# 25_LMS3_RX1_BB_ADC.net
KiCad netlist of a schematic drawn in Altium Designer
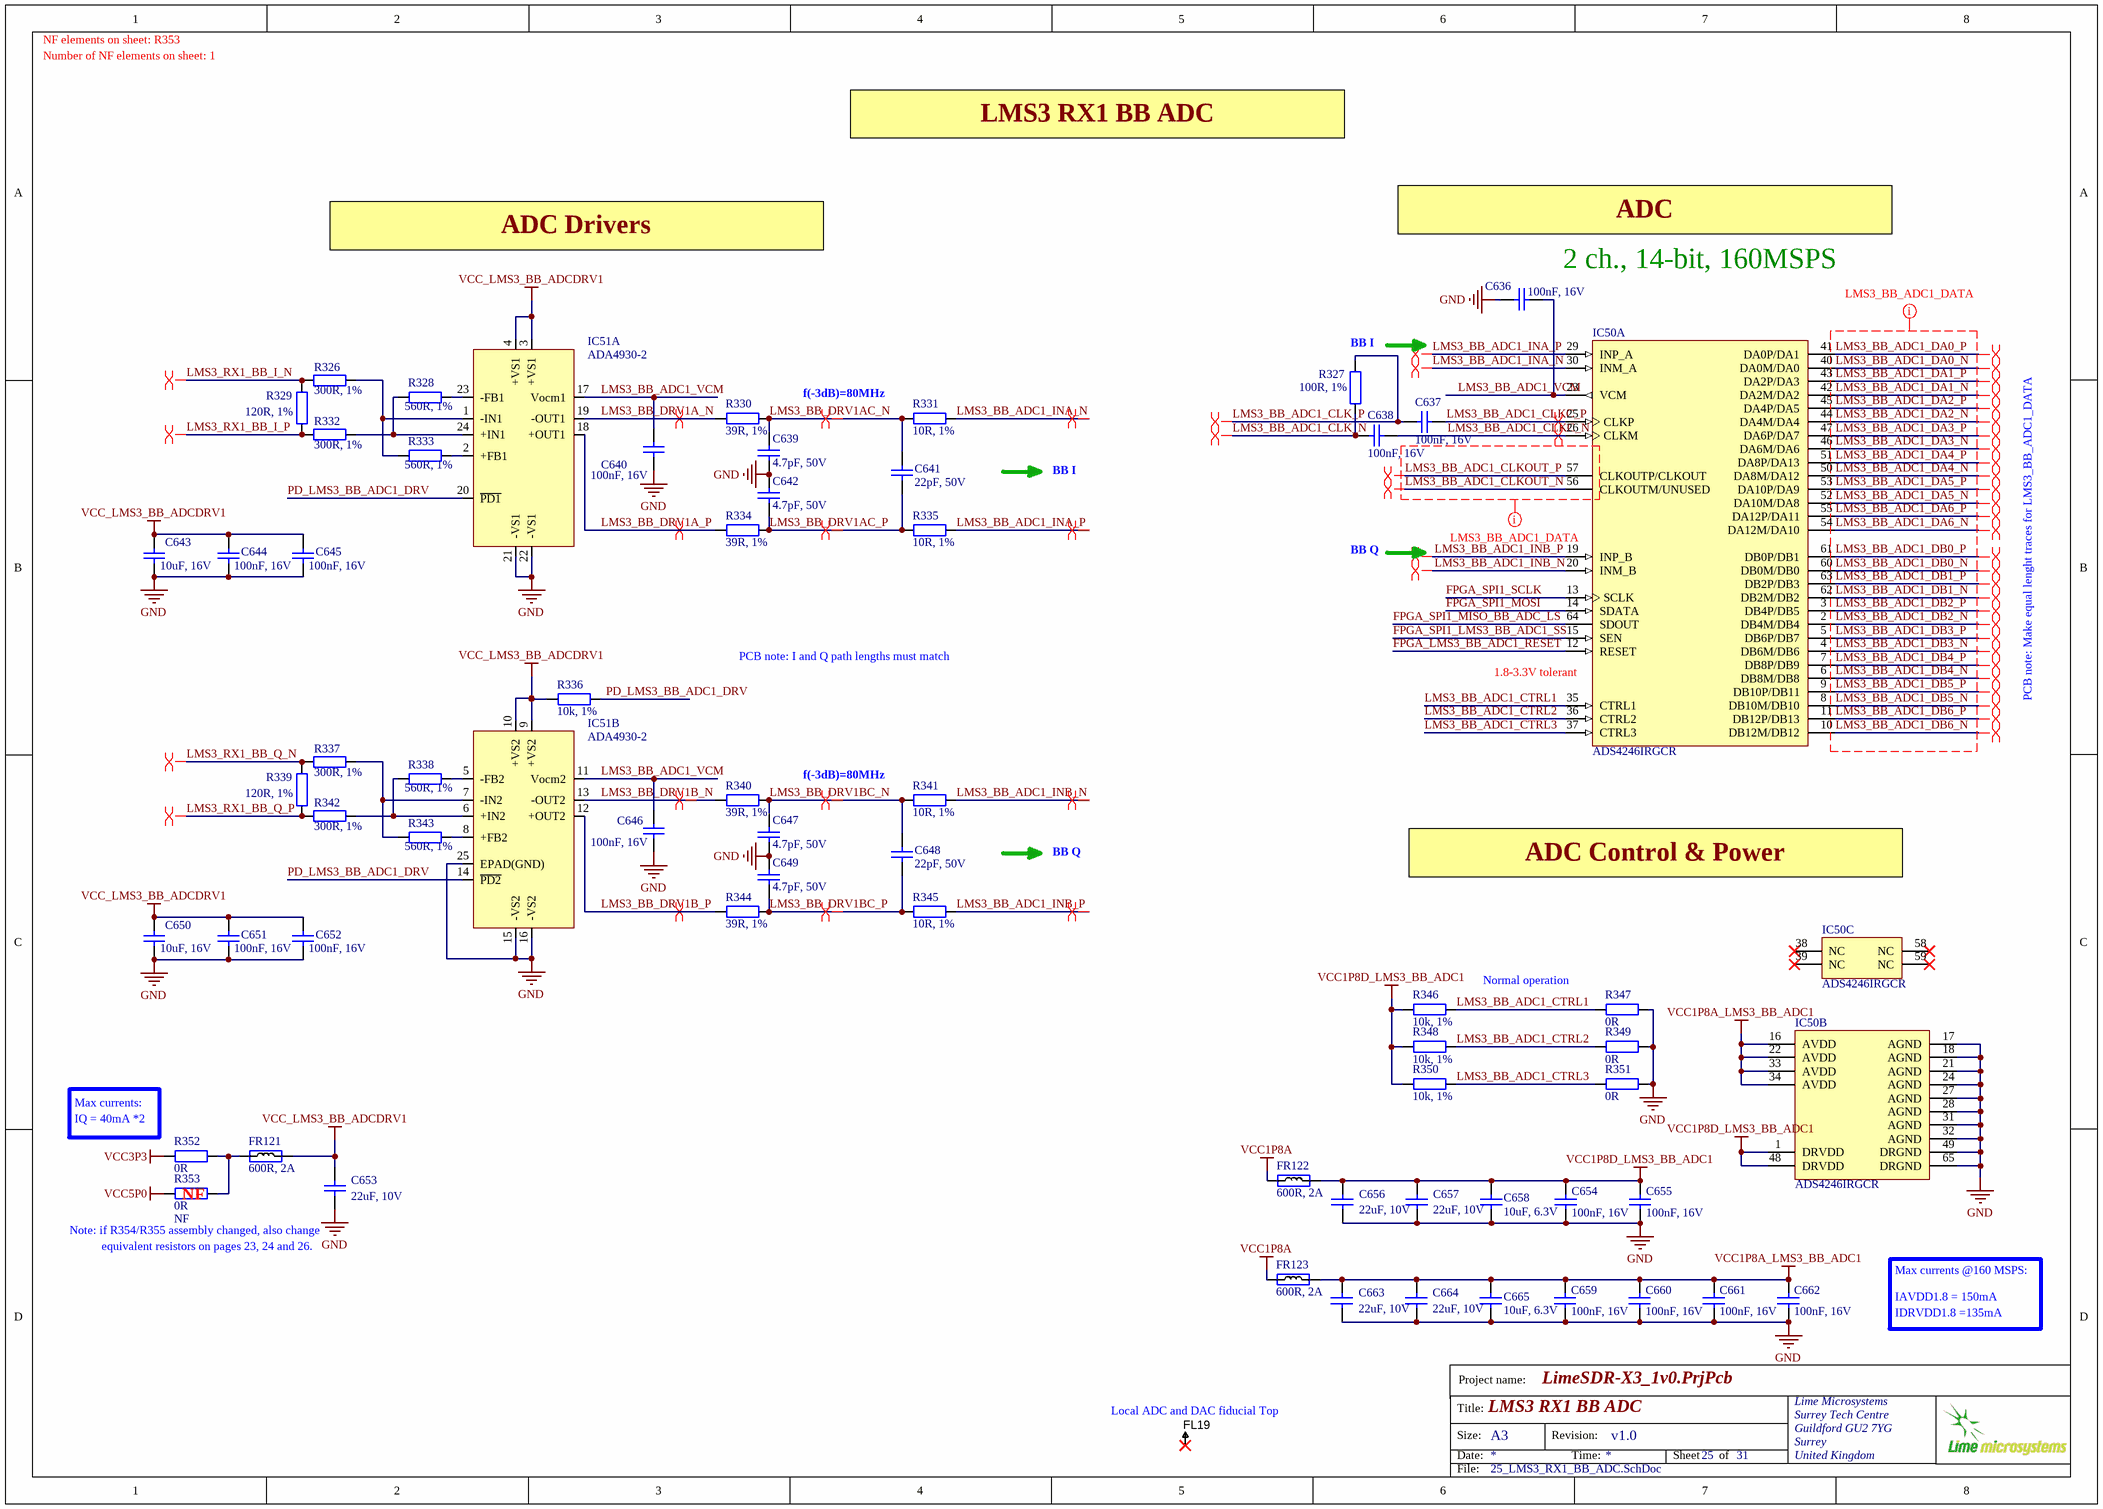
[diagram p0: 25_LMS3_RX1_BB_ADC.SchDoc]

(export (version "E")
  (design (tool "Eeschema 10.0.6"))
  (components
    (comp (ref "C636")
      (value "100nF, 16V")
      (footprint "CAP0402")
      (fields (field (name "TOLERANCE") "10 %") (field (name "MANUFACTURER") "Murata Electronics"))
      (libsource (lib "") (part "Cap_0603_3"))
    )
    (comp (ref "C637")
      (value "100nF, 16V")
      (footprint "CAP0402")
      (fields (field (name "TOLERANCE") "10 %") (field (name "MANUFACTURER") "Murata Electronics"))
      (libsource (lib "") (part "Cap_0603_3"))
    )
    (comp (ref "C638")
      (value "100nF, 16V")
      (footprint "CAP0402")
      (fields (field (name "TOLERANCE") "10 %") (field (name "MANUFACTURER") "Murata Electronics"))
      (libsource (lib "LimeFPGAboard_schLib") (part "Cap_0603"))
    )
    (comp (ref "C639")
      (value "4.7pF, 50V")
      (footprint "CAP0402")
      (fields (field (name "MANUFACTURER") "MURATA"))
      (libsource (lib "") (part "Cap_0402_1"))
    )
    (comp (ref "C640")
      (value "100nF, 16V")
      (footprint "CAP0402")
      (fields (field (name "TOLERANCE") "10 %") (field (name "MANUFACTURER") "Murata Electronics"))
      (libsource (lib "LimeFPGAboard_schLib") (part "Cap_0603"))
    )
    (comp (ref "C641")
      (value "22pF, 50V")
      (footprint "CAP0402")
      (fields (field (name "TOLERANCE") "±5%") (field (name "MANUFACTURER") "Yageo"))
      (libsource (lib "LimeMicroAltiumLib_schLib") (part "Cap_0402"))
    )
    (comp (ref "C642")
      (value "4.7pF, 50V")
      (footprint "CAP0402")
      (fields (field (name "MANUFACTURER") "MURATA"))
      (libsource (lib "") (part "Cap_0402_1"))
    )
    (comp (ref "C643")
      (value "10uF, 16V")
      (footprint "CAP0603")
      (fields (field (name "MANUFACTURER") "Yageo") (field (name "TOLERANCE") "±20%"))
      (libsource (lib "LimeMicroAltiumLib_schLib") (part "Cap_0603"))
    )
    (comp (ref "C644")
      (value "100nF, 16V")
      (footprint "CAP0402")
      (fields (field (name "TOLERANCE") "10 %") (field (name "MANUFACTURER") "Murata Electronics"))
      (libsource (lib "LimeFPGAboard_schLib") (part "Cap_0603"))
    )
    (comp (ref "C645")
      (value "100nF, 16V")
      (footprint "CAP0402")
      (fields (field (name "TOLERANCE") "10 %") (field (name "MANUFACTURER") "Murata Electronics"))
      (libsource (lib "LimeFPGAboard_schLib") (part "Cap_0603"))
    )
    (comp (ref "C646")
      (value "100nF, 16V")
      (footprint "CAP0402")
      (fields (field (name "TOLERANCE") "10 %") (field (name "MANUFACTURER") "Murata Electronics"))
      (libsource (lib "") (part "Cap_0603_4"))
    )
    (comp (ref "C647")
      (value "4.7pF, 50V")
      (footprint "CAP0402")
      (fields (field (name "MANUFACTURER") "MURATA"))
      (libsource (lib "") (part "Cap_0402_1"))
    )
    (comp (ref "C648")
      (value "22pF, 50V")
      (footprint "CAP0402")
      (fields (field (name "TOLERANCE") "±5%") (field (name "MANUFACTURER") "Yageo"))
      (libsource (lib "LimeMicroAltiumLib_schLib") (part "Cap_0402"))
    )
    (comp (ref "C649")
      (value "4.7pF, 50V")
      (footprint "CAP0402")
      (fields (field (name "MANUFACTURER") "MURATA"))
      (libsource (lib "") (part "Cap_0402_1"))
    )
    (comp (ref "C650")
      (value "10uF, 16V")
      (footprint "CAP0603")
      (fields (field (name "MANUFACTURER") "Yageo") (field (name "TOLERANCE") "±20%"))
      (libsource (lib "LimeMicroAltiumLib_schLib") (part "Cap_0603"))
    )
    (comp (ref "C651")
      (value "100nF, 16V")
      (footprint "CAP0402")
      (fields (field (name "TOLERANCE") "10 %") (field (name "MANUFACTURER") "Murata Electronics"))
      (libsource (lib "LimeFPGAboard_schLib") (part "Cap_0603"))
    )
    (comp (ref "C652")
      (value "100nF, 16V")
      (footprint "CAP0402")
      (fields (field (name "TOLERANCE") "10 %") (field (name "MANUFACTURER") "Murata Electronics"))
      (libsource (lib "LimeFPGAboard_schLib") (part "Cap_0603"))
    )
    (comp (ref "C653")
      (value "22uF, 10V")
      (footprint "CAP0603")
      (fields (field (name "TOLERANCE") "20 %") (field (name "MANUFACTURER") "TDK Corporation"))
      (libsource (lib "") (part "Cap_0603_5"))
    )
    (comp (ref "C654")
      (value "100nF, 16V")
      (footprint "CAP0402")
      (fields (field (name "TOLERANCE") "10 %") (field (name "MANUFACTURER") "Murata Electronics"))
      (libsource (lib "") (part "Cap_0603_2"))
    )
    (comp (ref "C655")
      (value "100nF, 16V")
      (footprint "CAP0402")
      (fields (field (name "TOLERANCE") "10 %") (field (name "MANUFACTURER") "Murata Electronics"))
      (libsource (lib "") (part "Cap_0603_2"))
    )
    (comp (ref "C656")
      (value "22uF, 10V")
      (footprint "CAP0603")
      (fields (field (name "TOLERANCE") "20 %") (field (name "MANUFACTURER") "TDK Corporation"))
      (libsource (lib "") (part "Cap_0603_2"))
    )
    (comp (ref "C657")
      (value "22uF, 10V")
      (footprint "CAP0603")
      (fields (field (name "TOLERANCE") "20 %") (field (name "MANUFACTURER") "TDK Corporation"))
      (libsource (lib "") (part "Cap_0603_2"))
    )
    (comp (ref "C658")
      (value "10uF, 6.3V")
      (footprint "CAP0603")
      (fields (field (name "TOLERANCE") "±20%") (field (name "MANUFACTURER") "Yageo"))
      (libsource (lib "") (part "Cap_0603_7"))
    )
    (comp (ref "C659")
      (value "100nF, 16V")
      (footprint "CAP0402")
      (fields (field (name "TOLERANCE") "10 %") (field (name "MANUFACTURER") "Murata Electronics"))
      (libsource (lib "") (part "Cap_0603_1"))
    )
    (comp (ref "C660")
      (value "100nF, 16V")
      (footprint "CAP0402")
      (fields (field (name "TOLERANCE") "10 %") (field (name "MANUFACTURER") "Murata Electronics"))
      (libsource (lib "") (part "Cap_0603_1"))
    )
    (comp (ref "C661")
      (value "100nF, 16V")
      (footprint "CAP0402")
      (fields (field (name "TOLERANCE") "10 %") (field (name "MANUFACTURER") "Murata Electronics"))
      (libsource (lib "") (part "Cap_0603_1"))
    )
    (comp (ref "C662")
      (value "100nF, 16V")
      (footprint "CAP0402")
      (fields (field (name "TOLERANCE") "10 %") (field (name "MANUFACTURER") "Murata Electronics"))
      (libsource (lib "") (part "Cap_0603_1"))
    )
    (comp (ref "C663")
      (value "22uF, 10V")
      (footprint "CAP0603")
      (fields (field (name "TOLERANCE") "20 %") (field (name "MANUFACTURER") "TDK Corporation"))
      (libsource (lib "") (part "Cap_0603_1"))
    )
    (comp (ref "C664")
      (value "22uF, 10V")
      (footprint "CAP0603")
      (fields (field (name "TOLERANCE") "20 %") (field (name "MANUFACTURER") "TDK Corporation"))
      (libsource (lib "") (part "Cap_0603_1"))
    )
    (comp (ref "C665")
      (value "10uF, 6.3V")
      (footprint "CAP0603")
      (fields (field (name "TOLERANCE") "±20%") (field (name "MANUFACTURER") "Yageo"))
      (libsource (lib "") (part "Cap_0603_6"))
    )
    (comp (ref "FL19")
      (value "Fiducial")
      (footprint "Fiducial_local")
      (libsource (lib "LimeMicroAltiumLib_schLib") (part "Fiducial"))
    )
    (comp (ref "FR121")
      (value "600R, 2A")
      (footprint "RES0805")
      (fields (field (name "MANUFACTURER") "TDK Corporation"))
      (libsource (lib "LimeMicroAltiumLib_schLib") (part "Ferrite"))
    )
    (comp (ref "FR122")
      (value "600R, 2A")
      (footprint "RES0805")
      (fields (field (name "MANUFACTURER") "TDK Corporation"))
      (libsource (lib "LimeFPGAboard_schLib") (part "Ferrite"))
    )
    (comp (ref "FR123")
      (value "600R, 2A")
      (footprint "RES0805")
      (fields (field (name "MANUFACTURER") "TDK Corporation"))
      (libsource (lib "LimeFPGAboard_schLib") (part "Ferrite"))
    )
    (comp (ref "IC50")
      (value "ADS4246IRGCR")
      (footprint "TI-RGC64-7400X7400TP_V")
      (description "14-Bit 160 MSPS Dual Low Power ADC, -40 to 85 degC, 64-pin QFN (RGC64), Green (RoHS & no Sb/Br)")
      (fields (field (name "MANUFACTURER") "Texas Instruments"))
      (libsource (lib "") (part "ADS4246IRGCR_1"))
    )
    (comp (ref "IC51")
      (value "ADA4930-2")
      (footprint "ADA4930-2_LFCSP-24")
      (fields (field (name "MANUFACTURER") "Analog Devices Inc."))
      (libsource (lib "") (part "ADA4930-2_1"))
    )
    (comp (ref "R326")
      (value "300R, 1%")
      (footprint "RES0402")
      (fields (field (name "TOLERANCE") "±1%") (field (name "MANUFACTURER") "Vishay Dale"))
      (libsource (lib "LimeFPGAboard_schLib") (part "Res_0402"))
    )
    (comp (ref "R327")
      (value "100R, 1%")
      (footprint "RES0402")
      (fields (field (name "TOLERANCE") "±1%") (field (name "MANUFACTURER") "Stackpole Electronics Inc."))
      (libsource (lib "LimeFPGAboard_schLib") (part "Res_0402"))
    )
    (comp (ref "R328")
      (value "560R, 1%")
      (footprint "RES0402")
      (fields (field (name "TOLERANCE") "±1%") (field (name "MANUFACTURER") "Vishay Dale"))
      (libsource (lib "LimeFPGAboard_schLib") (part "Res_0402"))
    )
    (comp (ref "R329")
      (value "120R, 1%")
      (footprint "RES0402")
      (fields (field (name "MANUFACTURER") "Yageo") (field (name "TOLERANCE") "1%"))
      (libsource (lib "") (part "Res_0402_1"))
    )
    (comp (ref "R330")
      (value "39R, 1%")
      (footprint "RES0402")
      (fields (field (name "MANUFACTURER") "Yageo") (field (name "TOLERANCE") "1%"))
      (libsource (lib "LimeMicroAltiumLib_schLib") (part "Res_0402"))
    )
    (comp (ref "R331")
      (value "10R, 1%")
      (footprint "RES0402")
      (fields (field (name "TOLERANCE") "1%"))
      (libsource (lib "LimeMicroAltiumLib_schLib") (part "Res_0402"))
    )
    (comp (ref "R332")
      (value "300R, 1%")
      (footprint "RES0402")
      (fields (field (name "TOLERANCE") "±1%") (field (name "MANUFACTURER") "Vishay Dale"))
      (libsource (lib "LimeFPGAboard_schLib") (part "Res_0402"))
    )
    (comp (ref "R333")
      (value "560R, 1%")
      (footprint "RES0402")
      (fields (field (name "TOLERANCE") "±1%") (field (name "MANUFACTURER") "Vishay Dale"))
      (libsource (lib "LimeFPGAboard_schLib") (part "Res_0402"))
    )
    (comp (ref "R334")
      (value "39R, 1%")
      (footprint "RES0402")
      (fields (field (name "MANUFACTURER") "Yageo") (field (name "TOLERANCE") "1%"))
      (libsource (lib "LimeMicroAltiumLib_schLib") (part "Res_0402"))
    )
    (comp (ref "R335")
      (value "10R, 1%")
      (footprint "RES0402")
      (fields (field (name "TOLERANCE") "1%"))
      (libsource (lib "LimeMicroAltiumLib_schLib") (part "Res_0402"))
    )
    (comp (ref "R336")
      (value "10k, 1%")
      (footprint "RES0402")
      (fields (field (name "MANUFACTURER") "Yageo") (field (name "TOLERANCE") "±1%"))
      (libsource (lib "LimeMicroAltiumLib_schLib") (part "Res_0402"))
    )
    (comp (ref "R337")
      (value "300R, 1%")
      (footprint "RES0402")
      (fields (field (name "TOLERANCE") "±1%") (field (name "MANUFACTURER") "Vishay Dale"))
      (libsource (lib "LimeFPGAboard_schLib") (part "Res_0402"))
    )
    (comp (ref "R338")
      (value "560R, 1%")
      (footprint "RES0402")
      (fields (field (name "TOLERANCE") "±1%") (field (name "MANUFACTURER") "Vishay Dale"))
      (libsource (lib "LimeFPGAboard_schLib") (part "Res_0402"))
    )
    (comp (ref "R339")
      (value "120R, 1%")
      (footprint "RES0402")
      (fields (field (name "MANUFACTURER") "Yageo") (field (name "TOLERANCE") "1%"))
      (libsource (lib "") (part "Res_0402_1"))
    )
    (comp (ref "R340")
      (value "39R, 1%")
      (footprint "RES0402")
      (fields (field (name "MANUFACTURER") "Yageo") (field (name "TOLERANCE") "1%"))
      (libsource (lib "LimeMicroAltiumLib_schLib") (part "Res_0402"))
    )
    (comp (ref "R341")
      (value "10R, 1%")
      (footprint "RES0402")
      (fields (field (name "TOLERANCE") "1%"))
      (libsource (lib "LimeMicroAltiumLib_schLib") (part "Res_0402"))
    )
    (comp (ref "R342")
      (value "300R, 1%")
      (footprint "RES0402")
      (fields (field (name "TOLERANCE") "±1%") (field (name "MANUFACTURER") "Vishay Dale"))
      (libsource (lib "LimeFPGAboard_schLib") (part "Res_0402"))
    )
    (comp (ref "R343")
      (value "560R, 1%")
      (footprint "RES0402")
      (fields (field (name "TOLERANCE") "±1%") (field (name "MANUFACTURER") "Vishay Dale"))
      (libsource (lib "LimeFPGAboard_schLib") (part "Res_0402"))
    )
    (comp (ref "R344")
      (value "39R, 1%")
      (footprint "RES0402")
      (fields (field (name "MANUFACTURER") "Yageo") (field (name "TOLERANCE") "1%"))
      (libsource (lib "LimeMicroAltiumLib_schLib") (part "Res_0402"))
    )
    (comp (ref "R345")
      (value "10R, 1%")
      (footprint "RES0402")
      (fields (field (name "TOLERANCE") "1%"))
      (libsource (lib "LimeMicroAltiumLib_schLib") (part "Res_0402"))
    )
    (comp (ref "R346")
      (value "10k, 1%")
      (footprint "RES0402")
      (fields (field (name "MANUFACTURER") "Yageo") (field (name "TOLERANCE") "±1%"))
      (libsource (lib "LimeMicroAltiumLib_schLib") (part "Res_0402"))
    )
    (comp (ref "R347")
      (value "0R")
      (footprint "RES0402")
      (fields (field (name "MANUFACTURER") "Yageo"))
      (libsource (lib "LimeFPGAboard_schLib") (part "Res_0402"))
    )
    (comp (ref "R348")
      (value "10k, 1%")
      (footprint "RES0402")
      (fields (field (name "MANUFACTURER") "Yageo") (field (name "TOLERANCE") "±1%"))
      (libsource (lib "LimeMicroAltiumLib_schLib") (part "Res_0402"))
    )
    (comp (ref "R349")
      (value "0R")
      (footprint "RES0402")
      (fields (field (name "MANUFACTURER") "Yageo"))
      (libsource (lib "LimeFPGAboard_schLib") (part "Res_0402"))
    )
    (comp (ref "R350")
      (value "10k, 1%")
      (footprint "RES0402")
      (fields (field (name "MANUFACTURER") "Yageo") (field (name "TOLERANCE") "±1%"))
      (libsource (lib "LimeMicroAltiumLib_schLib") (part "Res_0402"))
    )
    (comp (ref "R351")
      (value "0R")
      (footprint "RES0402")
      (fields (field (name "MANUFACTURER") "Yageo"))
      (libsource (lib "LimeFPGAboard_schLib") (part "Res_0402"))
    )
    (comp (ref "R352")
      (value "0R")
      (footprint "RES0402")
      (fields (field (name "MANUFACTURER") "Yageo") (field (name "TOLERANCE") "Jumper"))
      (libsource (lib "LimeMicroAltiumLib_schLib") (part "Res_0402"))
    )
    (comp (ref "R353")
      (value "0R")
      (footprint "RES0402")
      (fields
        (field (name "ASSEMBLY INFO") "NF")
        (field (name "MANUFACTURER") "Yageo")
        (field (name "TOLERANCE") "Jumper")
      )
      (libsource (lib "LimeMicroAltiumLib_schLib") (part "Res_0402"))
    )
  )
  (nets
    (net (code "1") (name "/FPGA_LMS3_BB_ADC1_RESET") (class "Default")
      (node (ref "IC50") (pin "12") (pinfunction "RESET_12") (pintype "input"))
    )
    (net (code "2") (name "/FPGA_SPI1_LMS3_BB_ADC1_SS") (class "Default")
      (node (ref "IC50") (pin "15") (pinfunction "SEN_15") (pintype "input"))
    )
    (net (code "3") (name "/FPGA_SPI1_MISO_BB_ADC_LS") (class "Default")
      (node (ref "IC50") (pin "64") (pinfunction "SDOUT_64") (pintype "tri_state"))
    )
    (net (code "4") (name "/FPGA_SPI1_MOSI") (class "Default")
      (node (ref "IC50") (pin "14") (pinfunction "SDATA_14") (pintype "input"))
    )
    (net (code "5") (name "/FPGA_SPI1_SCLK") (class "Default")
      (node (ref "IC50") (pin "13") (pinfunction "SCLK_13") (pintype "input"))
    )
    (net (code "6") (name "/LMS3_BB_ADC1_CLKC_N") (class "Default")
      (node (ref "C638") (pin "1") (pinfunction "1_1") (pintype "passive"))
      (node (ref "IC50") (pin "26") (pinfunction "CLKM_26") (pintype "input"))
    )
    (net (code "7") (name "/LMS3_BB_ADC1_CLKC_P") (class "Default")
      (node (ref "C637") (pin "1") (pinfunction "1_1") (pintype "passive"))
      (node (ref "IC50") (pin "25") (pinfunction "CLKP_25") (pintype "input"))
    )
    (net (code "8") (name "/LMS3_BB_ADC1_CLKOUT_N") (class "Default")
      (node (ref "IC50") (pin "56") (pinfunction "CLKOUTM/UNUSED_56") (pintype "tri_state"))
    )
    (net (code "9") (name "/LMS3_BB_ADC1_CLKOUT_P") (class "Default")
      (node (ref "IC50") (pin "57") (pinfunction "CLKOUTP/CLKOUT_57") (pintype "tri_state"))
    )
    (net (code "10") (name "/LMS3_BB_ADC1_CLK_N") (class "Default")
      (node (ref "C638") (pin "2") (pinfunction "2_2") (pintype "passive"))
      (node (ref "R327") (pin "1") (pinfunction "1_1") (pintype "passive"))
    )
    (net (code "11") (name "/LMS3_BB_ADC1_CLK_P") (class "Default")
      (node (ref "C637") (pin "2") (pinfunction "2_2") (pintype "passive"))
      (node (ref "R327") (pin "2") (pinfunction "2_2") (pintype "passive"))
    )
    (net (code "12") (name "/LMS3_BB_ADC1_CTRL1") (class "Default")
      (node (ref "IC50") (pin "35") (pinfunction "CTRL1_35") (pintype "input"))
      (node (ref "R346") (pin "1") (pinfunction "1_1") (pintype "passive"))
      (node (ref "R347") (pin "2") (pinfunction "2_2") (pintype "passive"))
    )
    (net (code "13") (name "/LMS3_BB_ADC1_CTRL2") (class "Default")
      (node (ref "IC50") (pin "36") (pinfunction "CTRL2_36") (pintype "input"))
      (node (ref "R348") (pin "1") (pinfunction "1_1") (pintype "passive"))
      (node (ref "R349") (pin "2") (pinfunction "2_2") (pintype "passive"))
    )
    (net (code "14") (name "/LMS3_BB_ADC1_CTRL3") (class "Default")
      (node (ref "IC50") (pin "37") (pinfunction "CTRL3_37") (pintype "input"))
      (node (ref "R350") (pin "1") (pinfunction "1_1") (pintype "passive"))
      (node (ref "R351") (pin "2") (pinfunction "2_2") (pintype "passive"))
    )
    (net (code "15") (name "/LMS3_BB_ADC1_DA0_N") (class "Default")
      (node (ref "IC50") (pin "40") (pinfunction "DA0M/DA0_40") (pintype "tri_state"))
    )
    (net (code "16") (name "/LMS3_BB_ADC1_DA0_P") (class "Default")
      (node (ref "IC50") (pin "41") (pinfunction "DA0P/DA1_41") (pintype "tri_state"))
    )
    (net (code "17") (name "/LMS3_BB_ADC1_DA1_N") (class "Default")
      (node (ref "IC50") (pin "42") (pinfunction "DA2M/DA2_42") (pintype "tri_state"))
    )
    (net (code "18") (name "/LMS3_BB_ADC1_DA1_P") (class "Default")
      (node (ref "IC50") (pin "43") (pinfunction "DA2P/DA3_43") (pintype "tri_state"))
    )
    (net (code "19") (name "/LMS3_BB_ADC1_DA2_N") (class "Default")
      (node (ref "IC50") (pin "44") (pinfunction "DA4M/DA4_44") (pintype "tri_state"))
    )
    (net (code "20") (name "/LMS3_BB_ADC1_DA2_P") (class "Default")
      (node (ref "IC50") (pin "45") (pinfunction "DA4P/DA5_45") (pintype "tri_state"))
    )
    (net (code "21") (name "/LMS3_BB_ADC1_DA3_N") (class "Default")
      (node (ref "IC50") (pin "46") (pinfunction "DA6M/DA6_46") (pintype "tri_state"))
    )
    (net (code "22") (name "/LMS3_BB_ADC1_DA3_P") (class "Default")
      (node (ref "IC50") (pin "47") (pinfunction "DA6P/DA7_47") (pintype "tri_state"))
    )
    (net (code "23") (name "/LMS3_BB_ADC1_DA4_N") (class "Default")
      (node (ref "IC50") (pin "50") (pinfunction "DA8M/DA12_50") (pintype "tri_state"))
    )
    (net (code "24") (name "/LMS3_BB_ADC1_DA4_P") (class "Default")
      (node (ref "IC50") (pin "51") (pinfunction "DA8P/DA13_51") (pintype "tri_state"))
    )
    (net (code "25") (name "/LMS3_BB_ADC1_DA5_N") (class "Default")
      (node (ref "IC50") (pin "52") (pinfunction "DA10M/DA8_52") (pintype "tri_state"))
    )
    (net (code "26") (name "/LMS3_BB_ADC1_DA5_P") (class "Default")
      (node (ref "IC50") (pin "53") (pinfunction "DA10P/DA9_53") (pintype "tri_state"))
    )
    (net (code "27") (name "/LMS3_BB_ADC1_DA6_N") (class "Default")
      (node (ref "IC50") (pin "54") (pinfunction "DA12M/DA10_54") (pintype "tri_state"))
    )
    (net (code "28") (name "/LMS3_BB_ADC1_DA6_P") (class "Default")
      (node (ref "IC50") (pin "55") (pinfunction "DA12P/DA11_55") (pintype "tri_state"))
    )
    (net (code "29") (name "/LMS3_BB_ADC1_DB0_N") (class "Default")
      (node (ref "IC50") (pin "60") (pinfunction "DB0M/DB0_60") (pintype "tri_state"))
    )
    (net (code "30") (name "/LMS3_BB_ADC1_DB0_P") (class "Default")
      (node (ref "IC50") (pin "61") (pinfunction "DB0P/DB1_61") (pintype "tri_state"))
    )
    (net (code "31") (name "/LMS3_BB_ADC1_DB1_N") (class "Default")
      (node (ref "IC50") (pin "62") (pinfunction "DB2M/DB2_62") (pintype "tri_state"))
    )
    (net (code "32") (name "/LMS3_BB_ADC1_DB1_P") (class "Default")
      (node (ref "IC50") (pin "63") (pinfunction "DB2P/DB3_63") (pintype "tri_state"))
    )
    (net (code "33") (name "/LMS3_BB_ADC1_DB2_N") (class "Default")
      (node (ref "IC50") (pin "2") (pinfunction "DB4M/DB4_2") (pintype "tri_state"))
    )
    (net (code "34") (name "/LMS3_BB_ADC1_DB2_P") (class "Default")
      (node (ref "IC50") (pin "3") (pinfunction "DB4P/DB5_3") (pintype "tri_state"))
    )
    (net (code "35") (name "/LMS3_BB_ADC1_DB3_N") (class "Default")
      (node (ref "IC50") (pin "4") (pinfunction "DB6M/DB6_4") (pintype "tri_state"))
    )
    (net (code "36") (name "/LMS3_BB_ADC1_DB3_P") (class "Default")
      (node (ref "IC50") (pin "5") (pinfunction "DB6P/DB7_5") (pintype "tri_state"))
    )
    (net (code "37") (name "/LMS3_BB_ADC1_DB4_N") (class "Default")
      (node (ref "IC50") (pin "6") (pinfunction "DB8M/DB8_6") (pintype "tri_state"))
    )
    (net (code "38") (name "/LMS3_BB_ADC1_DB4_P") (class "Default")
      (node (ref "IC50") (pin "7") (pinfunction "DB8P/DB9_7") (pintype "tri_state"))
    )
    (net (code "39") (name "/LMS3_BB_ADC1_DB5_N") (class "Default")
      (node (ref "IC50") (pin "8") (pinfunction "DB10M/DB10_8") (pintype "tri_state"))
    )
    (net (code "40") (name "/LMS3_BB_ADC1_DB5_P") (class "Default")
      (node (ref "IC50") (pin "9") (pinfunction "DB10P/DB11_9") (pintype "tri_state"))
    )
    (net (code "41") (name "/LMS3_BB_ADC1_DB6_N") (class "Default")
      (node (ref "IC50") (pin "10") (pinfunction "DB12M/DB12_10") (pintype "tri_state"))
    )
    (net (code "42") (name "/LMS3_BB_ADC1_DB6_P") (class "Default")
      (node (ref "IC50") (pin "11") (pinfunction "DB12P/DB13_11") (pintype "tri_state"))
    )
    (net (code "43") (name "/LMS3_BB_ADC1_INA_N") (class "Default")
      (node (ref "IC50") (pin "30") (pinfunction "INM_A_30") (pintype "input"))
      (node (ref "R331") (pin "1") (pinfunction "1_1") (pintype "passive"))
    )
    (net (code "44") (name "/LMS3_BB_ADC1_INA_P") (class "Default")
      (node (ref "IC50") (pin "29") (pinfunction "INP_A_29") (pintype "input"))
      (node (ref "R335") (pin "1") (pinfunction "1_1") (pintype "passive"))
    )
    (net (code "45") (name "/LMS3_BB_ADC1_INB_N") (class "Default")
      (node (ref "IC50") (pin "20") (pinfunction "INM_B_20") (pintype "input"))
      (node (ref "R341") (pin "1") (pinfunction "1_1") (pintype "passive"))
    )
    (net (code "46") (name "/LMS3_BB_ADC1_INB_P") (class "Default")
      (node (ref "IC50") (pin "19") (pinfunction "INP_B_19") (pintype "input"))
      (node (ref "R345") (pin "1") (pinfunction "1_1") (pintype "passive"))
    )
    (net (code "47") (name "/LMS3_BB_ADC1_VCM") (class "Default")
      (node (ref "C636") (pin "2") (pinfunction "2_2") (pintype "passive"))
      (node (ref "C640") (pin "1") (pinfunction "1_1") (pintype "passive"))
      (node (ref "C646") (pin "1") (pinfunction "1_1") (pintype "passive"))
      (node (ref "IC50") (pin "23") (pinfunction "VCM_23") (pintype "output"))
      (node (ref "IC51") (pin "11") (pinfunction "Vocm2_11") (pintype "input"))
      (node (ref "IC51") (pin "17") (pinfunction "Vocm1_17") (pintype "input"))
    )
    (net (code "48") (name "/LMS3_BB_DRV1AC_N") (class "Default")
      (node (ref "C639") (pin "1") (pinfunction "1_1") (pintype "passive"))
      (node (ref "C641") (pin "1") (pinfunction "1_1") (pintype "passive"))
      (node (ref "R330") (pin "1") (pinfunction "1_1") (pintype "passive"))
      (node (ref "R331") (pin "2") (pinfunction "2_2") (pintype "passive"))
    )
    (net (code "49") (name "/LMS3_BB_DRV1AC_P") (class "Default")
      (node (ref "C641") (pin "2") (pinfunction "2_2") (pintype "passive"))
      (node (ref "C642") (pin "2") (pinfunction "2_2") (pintype "passive"))
      (node (ref "R334") (pin "1") (pinfunction "1_1") (pintype "passive"))
      (node (ref "R335") (pin "2") (pinfunction "2_2") (pintype "passive"))
    )
    (net (code "50") (name "/LMS3_BB_DRV1A_N") (class "Default")
      (node (ref "IC51") (pin "19") (pinfunction "-OUT1_19") (pintype "output"))
      (node (ref "R330") (pin "2") (pinfunction "2_2") (pintype "passive"))
    )
    (net (code "51") (name "/LMS3_BB_DRV1A_P") (class "Default")
      (node (ref "IC51") (pin "18") (pinfunction "+OUT1_18") (pintype "output"))
      (node (ref "R334") (pin "2") (pinfunction "2_2") (pintype "passive"))
    )
    (net (code "52") (name "/LMS3_BB_DRV1BC_N") (class "Default")
      (node (ref "C647") (pin "1") (pinfunction "1_1") (pintype "passive"))
      (node (ref "C648") (pin "1") (pinfunction "1_1") (pintype "passive"))
      (node (ref "R340") (pin "1") (pinfunction "1_1") (pintype "passive"))
      (node (ref "R341") (pin "2") (pinfunction "2_2") (pintype "passive"))
    )
    (net (code "53") (name "/LMS3_BB_DRV1BC_P") (class "Default")
      (node (ref "C648") (pin "2") (pinfunction "2_2") (pintype "passive"))
      (node (ref "C649") (pin "2") (pinfunction "2_2") (pintype "passive"))
      (node (ref "R344") (pin "1") (pinfunction "1_1") (pintype "passive"))
      (node (ref "R345") (pin "2") (pinfunction "2_2") (pintype "passive"))
    )
    (net (code "54") (name "/LMS3_BB_DRV1B_N") (class "Default")
      (node (ref "IC51") (pin "13") (pinfunction "-OUT2_13") (pintype "output"))
      (node (ref "R340") (pin "2") (pinfunction "2_2") (pintype "passive"))
    )
    (net (code "55") (name "/LMS3_BB_DRV1B_P") (class "Default")
      (node (ref "IC51") (pin "12") (pinfunction "+OUT2_12") (pintype "output"))
      (node (ref "R344") (pin "2") (pinfunction "2_2") (pintype "passive"))
    )
    (net (code "56") (name "/LMS3_RX1_BB_I_N") (class "Default")
      (node (ref "R326") (pin "2") (pinfunction "2_2") (pintype "passive"))
      (node (ref "R329") (pin "2") (pinfunction "2_2") (pintype "passive"))
    )
    (net (code "57") (name "/LMS3_RX1_BB_I_P") (class "Default")
      (node (ref "R329") (pin "1") (pinfunction "1_1") (pintype "passive"))
      (node (ref "R332") (pin "2") (pinfunction "2_2") (pintype "passive"))
    )
    (net (code "58") (name "/LMS3_RX1_BB_Q_N") (class "Default")
      (node (ref "R337") (pin "2") (pinfunction "2_2") (pintype "passive"))
      (node (ref "R339") (pin "2") (pinfunction "2_2") (pintype "passive"))
    )
    (net (code "59") (name "/LMS3_RX1_BB_Q_P") (class "Default")
      (node (ref "R339") (pin "1") (pinfunction "1_1") (pintype "passive"))
      (node (ref "R342") (pin "2") (pinfunction "2_2") (pintype "passive"))
    )
    (net (code "60") (name "/PD_LMS3_BB_ADC1_DRV") (class "Default")
      (node (ref "IC51") (pin "14") (pinfunction "~{PD2}_14") (pintype "input"))
      (node (ref "IC51") (pin "20") (pinfunction "~{PD1}_20") (pintype "input"))
      (node (ref "R336") (pin "1") (pinfunction "1_1") (pintype "passive"))
    )
    (net (code "61") (name "GND") (class "Default")
      (node (ref "C636") (pin "1") (pinfunction "1_1") (pintype "passive"))
      (node (ref "C639") (pin "2") (pinfunction "2_2") (pintype "passive"))
      (node (ref "C640") (pin "2") (pinfunction "2_2") (pintype "passive"))
      (node (ref "C642") (pin "1") (pinfunction "1_1") (pintype "passive"))
      (node (ref "C643") (pin "1") (pinfunction "1_1") (pintype "passive"))
      (node (ref "C644") (pin "2") (pinfunction "2_2") (pintype "passive"))
      (node (ref "C645") (pin "2") (pinfunction "2_2") (pintype "passive"))
      (node (ref "C646") (pin "2") (pinfunction "2_2") (pintype "passive"))
      (node (ref "C647") (pin "2") (pinfunction "2_2") (pintype "passive"))
      (node (ref "C649") (pin "1") (pinfunction "1_1") (pintype "passive"))
      (node (ref "C650") (pin "1") (pinfunction "1_1") (pintype "passive"))
      (node (ref "C651") (pin "2") (pinfunction "2_2") (pintype "passive"))
      (node (ref "C652") (pin "2") (pinfunction "2_2") (pintype "passive"))
      (node (ref "C653") (pin "1") (pinfunction "1_1") (pintype "passive"))
      (node (ref "C654") (pin "1") (pinfunction "1_1") (pintype "passive"))
      (node (ref "C655") (pin "1") (pinfunction "1_1") (pintype "passive"))
      (node (ref "C656") (pin "1") (pinfunction "1_1") (pintype "passive"))
      (node (ref "C657") (pin "1") (pinfunction "1_1") (pintype "passive"))
      (node (ref "C658") (pin "2") (pinfunction "2_2") (pintype "passive"))
      (node (ref "C659") (pin "1") (pinfunction "1_1") (pintype "passive"))
      (node (ref "C660") (pin "1") (pinfunction "1_1") (pintype "passive"))
      (node (ref "C661") (pin "1") (pinfunction "1_1") (pintype "passive"))
      (node (ref "C662") (pin "1") (pinfunction "1_1") (pintype "passive"))
      (node (ref "C663") (pin "1") (pinfunction "1_1") (pintype "passive"))
      (node (ref "C664") (pin "1") (pinfunction "1_1") (pintype "passive"))
      (node (ref "C665") (pin "2") (pinfunction "2_2") (pintype "passive"))
      (node (ref "IC50") (pin "17") (pinfunction "AGND_17") (pintype "power_in"))
      (node (ref "IC50") (pin "18") (pinfunction "AGND_18") (pintype "power_in"))
      (node (ref "IC50") (pin "21") (pinfunction "AGND_21") (pintype "power_in"))
      (node (ref "IC50") (pin "24") (pinfunction "AGND_24") (pintype "power_in"))
      (node (ref "IC50") (pin "27") (pinfunction "AGND_27") (pintype "power_in"))
      (node (ref "IC50") (pin "28") (pinfunction "AGND_28") (pintype "power_in"))
      (node (ref "IC50") (pin "31") (pinfunction "AGND_31") (pintype "power_in"))
      (node (ref "IC50") (pin "32") (pinfunction "AGND_32") (pintype "power_in"))
      (node (ref "IC50") (pin "49") (pinfunction "DRGND_49") (pintype "power_in"))
      (node (ref "IC50") (pin "65") (pinfunction "DRGND_65") (pintype "power_in"))
      (node (ref "IC51") (pin "15") (pinfunction "-VS2_15") (pintype "power_in"))
      (node (ref "IC51") (pin "16") (pinfunction "-VS2_16") (pintype "power_in"))
      (node (ref "IC51") (pin "21") (pinfunction "-VS1_21") (pintype "power_in"))
      (node (ref "IC51") (pin "22") (pinfunction "-VS1_22") (pintype "power_in"))
      (node (ref "IC51") (pin "25") (pinfunction "EPAD(GND)_25") (pintype "passive"))
      (node (ref "R347") (pin "1") (pinfunction "1_1") (pintype "passive"))
      (node (ref "R349") (pin "1") (pinfunction "1_1") (pintype "passive"))
      (node (ref "R351") (pin "1") (pinfunction "1_1") (pintype "passive"))
    )
    (net (code "62") (name "Net-(FR121-Pad1)") (class "Default")
      (node (ref "FR121") (pin "1") (pinfunction "1_1") (pintype "passive"))
      (node (ref "R352") (pin "1") (pinfunction "1_1") (pintype "passive"))
      (node (ref "R353") (pin "1") (pinfunction "1_1") (pintype "passive"))
    )
    (net (code "63") (name "Net-(IC51A-+FB1)") (class "Default")
      (node (ref "IC51") (pin "2") (pinfunction "+FB1_2") (pintype "output"))
      (node (ref "R333") (pin "1") (pinfunction "1_1") (pintype "passive"))
    )
    (net (code "64") (name "Net-(IC51A-+IN1)") (class "Default")
      (node (ref "IC51") (pin "24") (pinfunction "+IN1_24") (pintype "input"))
      (node (ref "R328") (pin "2") (pinfunction "2_2") (pintype "passive"))
      (node (ref "R332") (pin "1") (pinfunction "1_1") (pintype "passive"))
    )
    (net (code "65") (name "Net-(IC51A--FB1)") (class "Default")
      (node (ref "IC51") (pin "23") (pinfunction "-FB1_23") (pintype "output"))
      (node (ref "R328") (pin "1") (pinfunction "1_1") (pintype "passive"))
    )
    (net (code "66") (name "Net-(IC51A--IN1)") (class "Default")
      (node (ref "IC51") (pin "1") (pinfunction "-IN1_1") (pintype "input"))
      (node (ref "R326") (pin "1") (pinfunction "1_1") (pintype "passive"))
      (node (ref "R333") (pin "2") (pinfunction "2_2") (pintype "passive"))
    )
    (net (code "67") (name "Net-(IC51B-+FB2)") (class "Default")
      (node (ref "IC51") (pin "8") (pinfunction "+FB2_8") (pintype "output"))
      (node (ref "R343") (pin "1") (pinfunction "1_1") (pintype "passive"))
    )
    (net (code "68") (name "Net-(IC51B-+IN2)") (class "Default")
      (node (ref "IC51") (pin "6") (pinfunction "+IN2_6") (pintype "input"))
      (node (ref "R338") (pin "2") (pinfunction "2_2") (pintype "passive"))
      (node (ref "R342") (pin "1") (pinfunction "1_1") (pintype "passive"))
    )
    (net (code "69") (name "Net-(IC51B--FB2)") (class "Default")
      (node (ref "IC51") (pin "5") (pinfunction "-FB2_5") (pintype "output"))
      (node (ref "R338") (pin "1") (pinfunction "1_1") (pintype "passive"))
    )
    (net (code "70") (name "Net-(IC51B--IN2)") (class "Default")
      (node (ref "IC51") (pin "7") (pinfunction "-IN2_7") (pintype "input"))
      (node (ref "R337") (pin "1") (pinfunction "1_1") (pintype "passive"))
      (node (ref "R343") (pin "2") (pinfunction "2_2") (pintype "passive"))
    )
    (net (code "71") (name "VCC1P8A") (class "Default")
      (node (ref "FR122") (pin "1") (pinfunction "1_1") (pintype "passive"))
      (node (ref "FR123") (pin "1") (pinfunction "1_1") (pintype "passive"))
    )
    (net (code "72") (name "VCC1P8A_LMS3_BB_ADC1") (class "Default")
      (node (ref "C659") (pin "2") (pinfunction "2_2") (pintype "passive"))
      (node (ref "C660") (pin "2") (pinfunction "2_2") (pintype "passive"))
      (node (ref "C661") (pin "2") (pinfunction "2_2") (pintype "passive"))
      (node (ref "C662") (pin "2") (pinfunction "2_2") (pintype "passive"))
      (node (ref "C663") (pin "2") (pinfunction "2_2") (pintype "passive"))
      (node (ref "C664") (pin "2") (pinfunction "2_2") (pintype "passive"))
      (node (ref "C665") (pin "1") (pinfunction "1_1") (pintype "passive"))
      (node (ref "FR123") (pin "2") (pinfunction "2_2") (pintype "passive"))
      (node (ref "IC50") (pin "16") (pinfunction "AVDD_16") (pintype "power_in"))
      (node (ref "IC50") (pin "22") (pinfunction "AVDD_22") (pintype "power_in"))
      (node (ref "IC50") (pin "33") (pinfunction "AVDD_33") (pintype "power_in"))
      (node (ref "IC50") (pin "34") (pinfunction "AVDD_34") (pintype "power_in"))
    )
    (net (code "73") (name "VCC1P8D_LMS3_BB_ADC1") (class "Default")
      (node (ref "C654") (pin "2") (pinfunction "2_2") (pintype "passive"))
      (node (ref "C655") (pin "2") (pinfunction "2_2") (pintype "passive"))
      (node (ref "C656") (pin "2") (pinfunction "2_2") (pintype "passive"))
      (node (ref "C657") (pin "2") (pinfunction "2_2") (pintype "passive"))
      (node (ref "C658") (pin "1") (pinfunction "1_1") (pintype "passive"))
      (node (ref "FR122") (pin "2") (pinfunction "2_2") (pintype "passive"))
      (node (ref "IC50") (pin "1") (pinfunction "DRVDD_1") (pintype "power_in"))
      (node (ref "IC50") (pin "48") (pinfunction "DRVDD_48") (pintype "power_in"))
      (node (ref "R346") (pin "2") (pinfunction "2_2") (pintype "passive"))
      (node (ref "R348") (pin "2") (pinfunction "2_2") (pintype "passive"))
      (node (ref "R350") (pin "2") (pinfunction "2_2") (pintype "passive"))
    )
    (net (code "74") (name "VCC3P3") (class "Default")
      (node (ref "R352") (pin "2") (pinfunction "2_2") (pintype "passive"))
    )
    (net (code "75") (name "VCC5P0") (class "Default")
      (node (ref "R353") (pin "2") (pinfunction "2_2") (pintype "passive"))
    )
    (net (code "76") (name "VCC_LMS3_BB_ADCDRV1") (class "Default")
      (node (ref "C643") (pin "2") (pinfunction "2_2") (pintype "passive"))
      (node (ref "C644") (pin "1") (pinfunction "1_1") (pintype "passive"))
      (node (ref "C645") (pin "1") (pinfunction "1_1") (pintype "passive"))
      (node (ref "C650") (pin "2") (pinfunction "2_2") (pintype "passive"))
      (node (ref "C651") (pin "1") (pinfunction "1_1") (pintype "passive"))
      (node (ref "C652") (pin "1") (pinfunction "1_1") (pintype "passive"))
      (node (ref "C653") (pin "2") (pinfunction "2_2") (pintype "passive"))
      (node (ref "FR121") (pin "2") (pinfunction "2_2") (pintype "passive"))
      (node (ref "IC51") (pin "10") (pinfunction "+VS2_10") (pintype "power_in"))
      (node (ref "IC51") (pin "3") (pinfunction "+VS1_3") (pintype "power_in"))
      (node (ref "IC51") (pin "4") (pinfunction "+VS1_4") (pintype "power_in"))
      (node (ref "IC51") (pin "9") (pinfunction "+VS2_9") (pintype "power_in"))
      (node (ref "R336") (pin "2") (pinfunction "2_2") (pintype "passive"))
    )
    (net (code "77") (name "unconnected-(FL19-Pad1)") (class "Default")
      (node (ref "FL19") (pin "1") (pintype "passive+no_connect"))
    )
    (net (code "78") (name "unconnected-(IC50C-NC-Pad38)") (class "Default")
      (node (ref "IC50") (pin "38") (pinfunction "NC_38") (pintype "passive+no_connect"))
    )
    (net (code "79") (name "unconnected-(IC50C-NC-Pad39)") (class "Default")
      (node (ref "IC50") (pin "39") (pinfunction "NC_39") (pintype "passive+no_connect"))
    )
    (net (code "80") (name "unconnected-(IC50C-NC-Pad58)") (class "Default")
      (node (ref "IC50") (pin "58") (pinfunction "NC_58") (pintype "passive+no_connect"))
    )
    (net (code "81") (name "unconnected-(IC50C-NC-Pad59)") (class "Default")
      (node (ref "IC50") (pin "59") (pinfunction "NC_59") (pintype "passive+no_connect"))
    )
  )
)
